# Buffer.net
KiCad netlist of a schematic drawn in Altium Designer
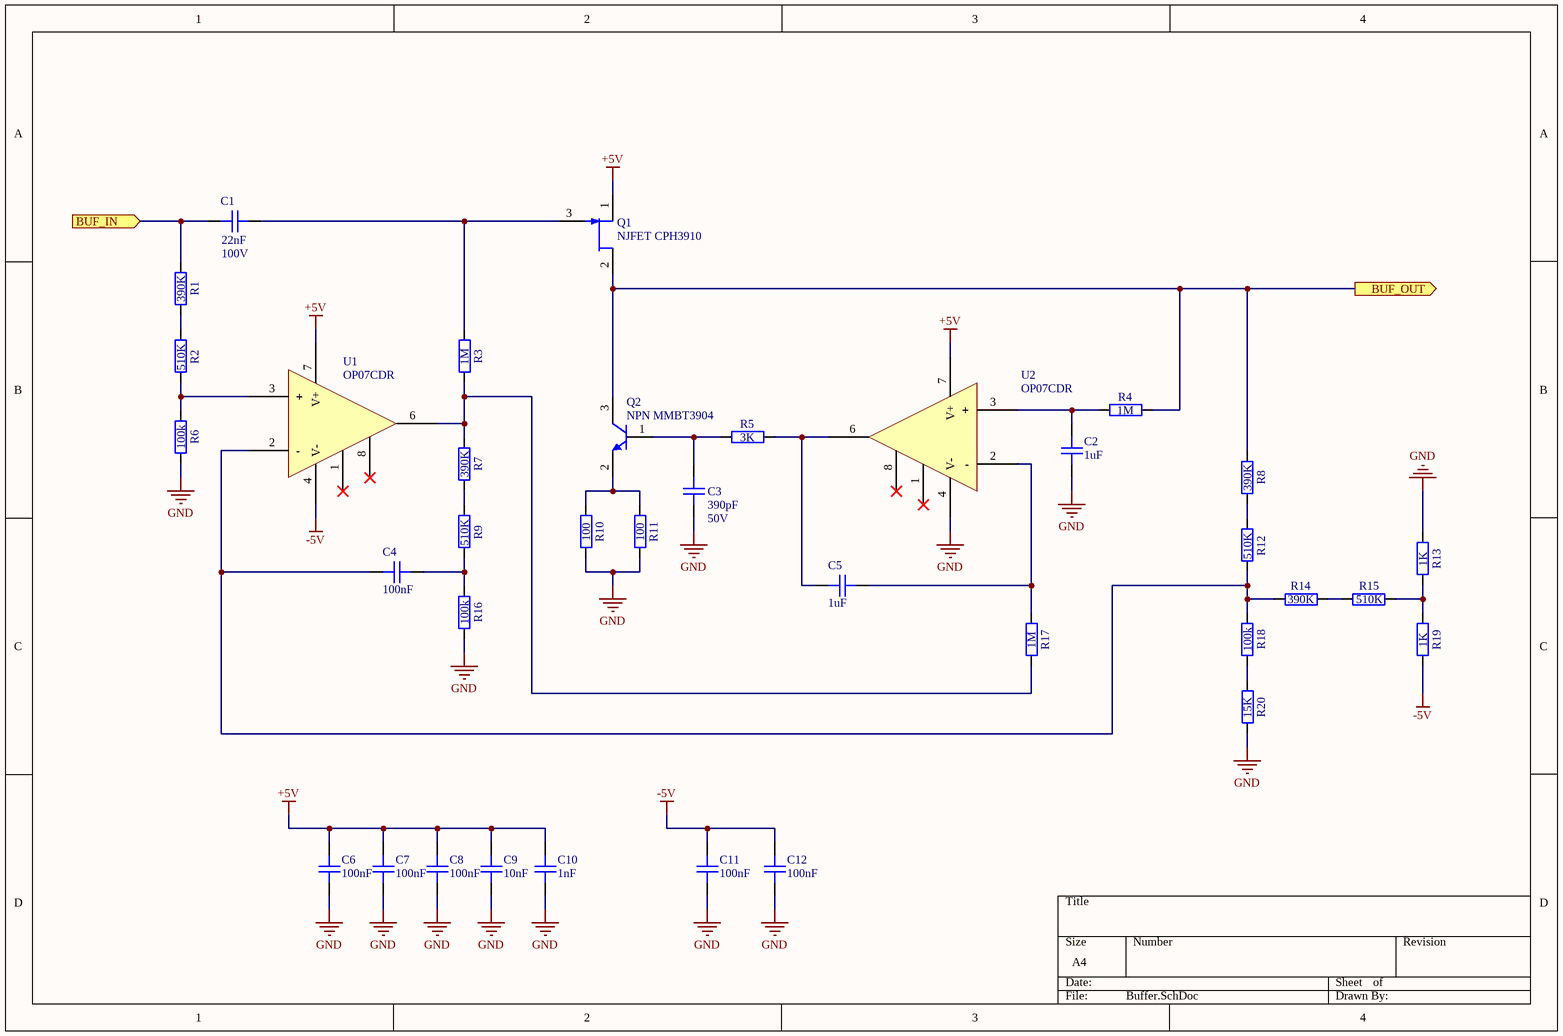
[diagram p0: Buffer.SchDoc]

(export (version "E")
  (design (tool "Eeschema 10.0.6"))
  (components
    (comp (ref "C1")
      (value "22nF")
      (footprint "GEN_C_0603")
      (fields (field (name "VOLTAGE RATING") "100V") (field (name "Comment") "CAP 22nF 100V X7R 0603"))
      (libsource (lib "DSO") (part "CAP 22nF 100V X7R 0603"))
    )
    (comp (ref "C2")
      (value "1uF")
      (footprint "GEN_C_0402")
      (fields (field (name "Comment") "CAP 1uF 25V X5R 0402"))
      (libsource (lib "DSO") (part "CAP 1uF 25V X5R 0402"))
    )
    (comp (ref "C3")
      (value "390pF")
      (footprint "GEN_C_0402")
      (fields (field (name "VOLTAGE RATING") "50V") (field (name "Comment") "CAP 390pF 50V C0G 0402"))
      (libsource (lib "DSO") (part "CAP 390pF 50V C0G 0402"))
    )
    (comp (ref "C4")
      (value "100nF")
      (footprint "GEN_C_0402")
      (fields (field (name "Comment") "CAP 100nF 16V X7R 0402"))
      (libsource (lib "DSO") (part "CAP 100nF 16V X7R 0402"))
    )
    (comp (ref "C5")
      (value "1uF")
      (footprint "GEN_C_0402")
      (fields (field (name "Comment") "CAP 1uF 25V X5R 0402"))
      (libsource (lib "DSO") (part "CAP 1uF 25V X5R 0402"))
    )
    (comp (ref "C6")
      (value "100nF")
      (footprint "GEN_C_0402")
      (fields (field (name "Comment") "CAP 100nF 16V X7R 0402"))
      (libsource (lib "DSO") (part "CAP 100nF 16V X7R 0402"))
    )
    (comp (ref "C7")
      (value "100nF")
      (footprint "GEN_C_0402")
      (fields (field (name "Comment") "CAP 100nF 16V X7R 0402"))
      (libsource (lib "DSO") (part "CAP 100nF 16V X7R 0402"))
    )
    (comp (ref "C8")
      (value "100nF")
      (footprint "GEN_C_0402")
      (fields (field (name "Comment") "CAP 100nF 16V X7R 0402"))
      (libsource (lib "DSO") (part "CAP 100nF 16V X7R 0402"))
    )
    (comp (ref "C9")
      (value "10nF")
      (footprint "GEN_C_0402")
      (fields (field (name "Comment") "CAP 10nF 50V X7R 0402"))
      (libsource (lib "DSO") (part "CAP 10nF 50V X7R 0402"))
    )
    (comp (ref "C10")
      (value "1nF")
      (footprint "GEN_C_0402")
      (fields (field (name "Comment") "CAP 1nF 50V X7R 0402"))
      (libsource (lib "DSO") (part "CAP 1nF 50V X7R 0402"))
    )
    (comp (ref "C11")
      (value "100nF")
      (footprint "GEN_C_0402")
      (fields (field (name "Comment") "CAP 100nF 16V X7R 0402"))
      (libsource (lib "DSO") (part "CAP 100nF 16V X7R 0402"))
    )
    (comp (ref "C12")
      (value "100nF")
      (footprint "GEN_C_0402")
      (fields (field (name "Comment") "CAP 100nF 16V X7R 0402"))
      (libsource (lib "DSO") (part "CAP 100nF 16V X7R 0402"))
    )
    (comp (ref "Q1")
      (value "NJFET CPH3910")
      (footprint "ON_SOT23_CPH3")
      (libsource (lib "DSO") (part "NJFET CPH3910"))
    )
    (comp (ref "Q2")
      (value "NPN MMBT3904")
      (footprint "MMC_SOT23")
      (libsource (lib "DSO") (part "NPN MMBT3904"))
    )
    (comp (ref "R1")
      (value "390K")
      (footprint "GEN_R_0402")
      (fields (field (name "TOLERANCE") "1%") (field (name "Comment") "RES 390K OHM 1% 1/10W 0402"))
      (libsource (lib "DSO") (part "RES 390K OHM 1% 1/10W 0402"))
    )
    (comp (ref "R2")
      (value "510K")
      (footprint "GEN_R_0402")
      (fields (field (name "TOLERANCE") "1%") (field (name "Comment") "RES 510K OHM 1% 1/10W 0402"))
      (libsource (lib "DSO") (part "RES 510K OHM 1% 1/10W 0402"))
    )
    (comp (ref "R3")
      (value "1M")
      (footprint "GEN_R_0402")
      (fields (field (name "TOLERANCE") "1%") (field (name "Comment") "RES 1M OHM 1% 1/10W 0402"))
      (libsource (lib "DSO") (part "RES 1M OHM 1% 1/10W 0402"))
    )
    (comp (ref "R4")
      (value "1M")
      (footprint "GEN_R_0402")
      (fields (field (name "TOLERANCE") "1%") (field (name "Comment") "RES 1M OHM 1% 1/10W 0402"))
      (libsource (lib "") (part "RES 1M OHM 1% 1/10W 0402_1"))
    )
    (comp (ref "R5")
      (value "3K")
      (footprint "GEN_R_0402")
      (fields (field (name "TOLERANCE") "1%") (field (name "Comment") "RES 3K OHM 1% 1/10W 0402"))
      (libsource (lib "DSO") (part "RES 3K OHM 1% 1/10W 0402"))
    )
    (comp (ref "R6")
      (value "100k")
      (footprint "GEN_R_0402")
      (fields (field (name "TOLERANCE") "1%") (field (name "Comment") "RES 100K OHM 1% 1/10W 0402"))
      (libsource (lib "DSO") (part "RES 100K OHM 1% 1/10W 0402"))
    )
    (comp (ref "R7")
      (value "390K")
      (footprint "GEN_R_0402")
      (fields (field (name "TOLERANCE") "1%") (field (name "Comment") "RES 390K OHM 1% 1/10W 0402"))
      (libsource (lib "DSO") (part "RES 390K OHM 1% 1/10W 0402"))
    )
    (comp (ref "R8")
      (value "390K")
      (footprint "GEN_R_0402")
      (fields (field (name "TOLERANCE") "1%") (field (name "Comment") "RES 390K OHM 1% 1/10W 0402"))
      (libsource (lib "DSO") (part "RES 390K OHM 1% 1/10W 0402"))
    )
    (comp (ref "R9")
      (value "510K")
      (footprint "GEN_R_0402")
      (fields (field (name "TOLERANCE") "1%") (field (name "Comment") "RES 510K OHM 1% 1/10W 0402"))
      (libsource (lib "DSO") (part "RES 510K OHM 1% 1/10W 0402"))
    )
    (comp (ref "R10")
      (value "100")
      (footprint "GEN_R_0402")
      (fields (field (name "TOLERANCE") "1%") (field (name "Comment") "RES 100 OHM 1% 1/10W 0402"))
      (libsource (lib "DSO") (part "RES 100 OHM 1% 1/10W 0402"))
    )
    (comp (ref "R11")
      (value "100")
      (footprint "GEN_R_0402")
      (fields (field (name "TOLERANCE") "1%") (field (name "Comment") "RES 100 OHM 1% 1/10W 0402"))
      (libsource (lib "DSO") (part "RES 100 OHM 1% 1/10W 0402"))
    )
    (comp (ref "R12")
      (value "510K")
      (footprint "GEN_R_0402")
      (fields (field (name "TOLERANCE") "1%") (field (name "Comment") "RES 510K OHM 1% 1/10W 0402"))
      (libsource (lib "DSO") (part "RES 510K OHM 1% 1/10W 0402"))
    )
    (comp (ref "R13")
      (value "1K")
      (footprint "GEN_R_0402")
      (fields (field (name "TOLERANCE") "1%") (field (name "Comment") "RES 1K OHM 1% 1/10W 0402"))
      (libsource (lib "DSO") (part "RES 1K OHM 1% 1/10W 0402"))
    )
    (comp (ref "R14")
      (value "390K")
      (footprint "GEN_R_0402")
      (fields (field (name "TOLERANCE") "1%") (field (name "Comment") "RES 390K OHM 1% 1/10W 0402"))
      (libsource (lib "") (part "RES 390K OHM 1% 1/10W 0402_1"))
    )
    (comp (ref "R15")
      (value "510K")
      (footprint "GEN_R_0402")
      (fields (field (name "TOLERANCE") "1%") (field (name "Comment") "RES 510K OHM 1% 1/10W 0402"))
      (libsource (lib "") (part "RES 510K OHM 1% 1/10W 0402_1"))
    )
    (comp (ref "R16")
      (value "100k")
      (footprint "GEN_R_0402")
      (fields (field (name "TOLERANCE") "1%") (field (name "Comment") "RES 100K OHM 1% 1/10W 0402"))
      (libsource (lib "DSO") (part "RES 100K OHM 1% 1/10W 0402"))
    )
    (comp (ref "R17")
      (value "1M")
      (footprint "GEN_R_0402")
      (fields (field (name "TOLERANCE") "1%") (field (name "Comment") "RES 1M OHM 1% 1/10W 0402"))
      (libsource (lib "DSO") (part "RES 1M OHM 1% 1/10W 0402"))
    )
    (comp (ref "R18")
      (value "100k")
      (footprint "GEN_R_0402")
      (fields (field (name "TOLERANCE") "1%") (field (name "Comment") "RES 100K OHM 1% 1/10W 0402"))
      (libsource (lib "DSO") (part "RES 100K OHM 1% 1/10W 0402"))
    )
    (comp (ref "R19")
      (value "1K")
      (footprint "GEN_R_0402")
      (fields (field (name "TOLERANCE") "1%") (field (name "Comment") "RES 1K OHM 1% 1/10W 0402"))
      (libsource (lib "DSO") (part "RES 1K OHM 1% 1/10W 0402"))
    )
    (comp (ref "R20")
      (value "15K")
      (footprint "GEN_R_0402")
      (fields (field (name "TOLERANCE") "1%") (field (name "Comment") "RES 15K OHM 1% 1/10W 0402"))
      (libsource (lib "DSO") (part "RES 15K OHM 1% 1/10W 0402"))
    )
    (comp (ref "U1")
      (value "OP07CDR")
      (footprint "TI_SOIC8_D0008A")
      (libsource (lib "DSO") (part "IC OPAMP OP07CDR"))
    )
    (comp (ref "U2")
      (value "OP07CDR")
      (footprint "TI_SOIC8_D0008A")
      (libsource (lib "DSO") (part "IC OPAMP OP07CDR"))
    )
  )
  (nets
    (net (code "1") (name "+5V") (class "Default")
      (node (ref "C10") (pin "2") (pinfunction "2_2") (pintype "passive"))
      (node (ref "C6") (pin "1") (pinfunction "1_1") (pintype "passive"))
      (node (ref "C7") (pin "1") (pinfunction "1_1") (pintype "passive"))
      (node (ref "C8") (pin "1") (pinfunction "1_1") (pintype "passive"))
      (node (ref "C9") (pin "2") (pinfunction "2_2") (pintype "passive"))
      (node (ref "Q1") (pin "1") (pinfunction "S_1") (pintype "passive"))
      (node (ref "U1") (pin "7") (pinfunction "V+_7") (pintype "passive"))
      (node (ref "U2") (pin "7") (pinfunction "V+_7") (pintype "passive"))
    )
    (net (code "2") (name "-5V") (class "Default")
      (node (ref "C11") (pin "1") (pinfunction "1_1") (pintype "passive"))
      (node (ref "C12") (pin "1") (pinfunction "1_1") (pintype "passive"))
      (node (ref "R19") (pin "2") (pinfunction "2_2") (pintype "passive"))
      (node (ref "U1") (pin "4") (pinfunction "V-_4") (pintype "passive"))
    )
    (net (code "3") (name "/BUF_IN") (class "Default")
      (node (ref "C1") (pin "2") (pinfunction "2_2") (pintype "passive"))
      (node (ref "R1") (pin "1") (pinfunction "1_1") (pintype "passive"))
    )
    (net (code "4") (name "/BUF_OUT") (class "Default")
      (node (ref "Q1") (pin "2") (pinfunction "D_2") (pintype "passive"))
      (node (ref "Q2") (pin "3") (pinfunction "C_3") (pintype "passive"))
      (node (ref "R4") (pin "1") (pinfunction "1_1") (pintype "passive"))
      (node (ref "R8") (pin "1") (pinfunction "1_1") (pintype "passive"))
    )
    (net (code "5") (name "GND") (class "Default")
      (node (ref "C10") (pin "1") (pinfunction "1_1") (pintype "passive"))
      (node (ref "C11") (pin "2") (pinfunction "2_2") (pintype "passive"))
      (node (ref "C12") (pin "2") (pinfunction "2_2") (pintype "passive"))
      (node (ref "C2") (pin "1") (pinfunction "1_1") (pintype "passive"))
      (node (ref "C3") (pin "1") (pinfunction "1_1") (pintype "passive"))
      (node (ref "C6") (pin "2") (pinfunction "2_2") (pintype "passive"))
      (node (ref "C7") (pin "2") (pinfunction "2_2") (pintype "passive"))
      (node (ref "C8") (pin "2") (pinfunction "2_2") (pintype "passive"))
      (node (ref "C9") (pin "1") (pinfunction "1_1") (pintype "passive"))
      (node (ref "R10") (pin "1") (pinfunction "1_1") (pintype "passive"))
      (node (ref "R11") (pin "1") (pinfunction "1_1") (pintype "passive"))
      (node (ref "R13") (pin "1") (pinfunction "1_1") (pintype "passive"))
      (node (ref "R16") (pin "2") (pinfunction "2_2") (pintype "passive"))
      (node (ref "R20") (pin "1") (pinfunction "1_1") (pintype "passive"))
      (node (ref "R6") (pin "2") (pinfunction "2_2") (pintype "passive"))
      (node (ref "U2") (pin "4") (pinfunction "V-_4") (pintype "passive"))
    )
    (net (code "6") (name "Net-(C4-Pad1)") (class "Default")
      (node (ref "C4") (pin "1") (pinfunction "1_1") (pintype "passive"))
      (node (ref "R16") (pin "1") (pinfunction "1_1") (pintype "passive"))
      (node (ref "R9") (pin "2") (pinfunction "2_2") (pintype "passive"))
    )
    (net (code "7") (name "Net-(Q1-G)") (class "Default")
      (node (ref "C1") (pin "1") (pinfunction "1_1") (pintype "passive"))
      (node (ref "Q1") (pin "3") (pinfunction "G_3") (pintype "passive"))
      (node (ref "R3") (pin "2") (pinfunction "2_2") (pintype "passive"))
    )
    (net (code "8") (name "Net-(Q2-B)") (class "Default")
      (node (ref "C3") (pin "2") (pinfunction "2_2") (pintype "passive"))
      (node (ref "Q2") (pin "1") (pinfunction "B_1") (pintype "passive"))
      (node (ref "R5") (pin "2") (pinfunction "2_2") (pintype "passive"))
    )
    (net (code "9") (name "Net-(Q2-E)") (class "Default")
      (node (ref "Q2") (pin "2") (pinfunction "E_2") (pintype "passive"))
      (node (ref "R10") (pin "2") (pinfunction "2_2") (pintype "passive"))
      (node (ref "R11") (pin "2") (pinfunction "2_2") (pintype "passive"))
    )
    (net (code "10") (name "Net-(R1-Pad2)") (class "Default")
      (node (ref "R1") (pin "2") (pinfunction "2_2") (pintype "passive"))
      (node (ref "R2") (pin "1") (pinfunction "1_1") (pintype "passive"))
    )
    (net (code "11") (name "Net-(R7-Pad2)") (class "Default")
      (node (ref "R7") (pin "2") (pinfunction "2_2") (pintype "passive"))
      (node (ref "R9") (pin "1") (pinfunction "1_1") (pintype "passive"))
    )
    (net (code "12") (name "Net-(R12-Pad1)") (class "Default")
      (node (ref "R12") (pin "1") (pinfunction "1_1") (pintype "passive"))
      (node (ref "R8") (pin "2") (pinfunction "2_2") (pintype "passive"))
    )
    (net (code "13") (name "Net-(R13-Pad2)") (class "Default")
      (node (ref "R13") (pin "2") (pinfunction "2_2") (pintype "passive"))
      (node (ref "R15") (pin "2") (pinfunction "2_2") (pintype "passive"))
      (node (ref "R19") (pin "1") (pinfunction "1_1") (pintype "passive"))
    )
    (net (code "14") (name "Net-(R14-Pad2)") (class "Default")
      (node (ref "R14") (pin "2") (pinfunction "2_2") (pintype "passive"))
      (node (ref "R15") (pin "1") (pinfunction "1_1") (pintype "passive"))
    )
    (net (code "15") (name "Net-(R18-Pad2)") (class "Default")
      (node (ref "R18") (pin "2") (pinfunction "2_2") (pintype "passive"))
      (node (ref "R20") (pin "2") (pinfunction "2_2") (pintype "passive"))
    )
    (net (code "16") (name "Net-(U1-+)") (class "Default")
      (node (ref "R2") (pin "2") (pinfunction "2_2") (pintype "passive"))
      (node (ref "R6") (pin "1") (pinfunction "1_1") (pintype "passive"))
      (node (ref "U1") (pin "3") (pinfunction "+_3") (pintype "passive"))
    )
    (net (code "17") (name "Net-(U1--)") (class "Default")
      (node (ref "C4") (pin "2") (pinfunction "2_2") (pintype "passive"))
      (node (ref "R12") (pin "2") (pinfunction "2_2") (pintype "passive"))
      (node (ref "R14") (pin "1") (pinfunction "1_1") (pintype "passive"))
      (node (ref "R18") (pin "1") (pinfunction "1_1") (pintype "passive"))
      (node (ref "U1") (pin "2") (pinfunction "-_2") (pintype "passive"))
    )
    (net (code "18") (name "Net-(U1-OUT)") (class "Default")
      (node (ref "R17") (pin "1") (pinfunction "1_1") (pintype "passive"))
      (node (ref "R3") (pin "1") (pinfunction "1_1") (pintype "passive"))
      (node (ref "R7") (pin "1") (pinfunction "1_1") (pintype "passive"))
      (node (ref "U1") (pin "6") (pinfunction "OUT_6") (pintype "passive"))
    )
    (net (code "19") (name "Net-(U2-+)") (class "Default")
      (node (ref "C2") (pin "2") (pinfunction "2_2") (pintype "passive"))
      (node (ref "R4") (pin "2") (pinfunction "2_2") (pintype "passive"))
      (node (ref "U2") (pin "3") (pinfunction "+_3") (pintype "passive"))
    )
    (net (code "20") (name "Net-(U2--)") (class "Default")
      (node (ref "C5") (pin "1") (pinfunction "1_1") (pintype "passive"))
      (node (ref "R17") (pin "2") (pinfunction "2_2") (pintype "passive"))
      (node (ref "U2") (pin "2") (pinfunction "-_2") (pintype "passive"))
    )
    (net (code "21") (name "Net-(U2-OUT)") (class "Default")
      (node (ref "C5") (pin "2") (pinfunction "2_2") (pintype "passive"))
      (node (ref "R5") (pin "1") (pinfunction "1_1") (pintype "passive"))
      (node (ref "U2") (pin "6") (pinfunction "OUT_6") (pintype "passive"))
    )
    (net (code "22") (name "unconnected-(U1-N1-Pad1)") (class "Default")
      (node (ref "U1") (pin "1") (pinfunction "N1_1") (pintype "passive+no_connect"))
    )
    (net (code "23") (name "unconnected-(U1-N2-Pad8)") (class "Default")
      (node (ref "U1") (pin "8") (pinfunction "N2_8") (pintype "passive+no_connect"))
    )
    (net (code "24") (name "unconnected-(U2-N1-Pad1)") (class "Default")
      (node (ref "U2") (pin "1") (pinfunction "N1_1") (pintype "passive+no_connect"))
    )
    (net (code "25") (name "unconnected-(U2-N2-Pad8)") (class "Default")
      (node (ref "U2") (pin "8") (pinfunction "N2_8") (pintype "passive+no_connect"))
    )
  )
)
